# pcb_v1_4.net
KiCad netlist of a schematic drawn in EAGLE
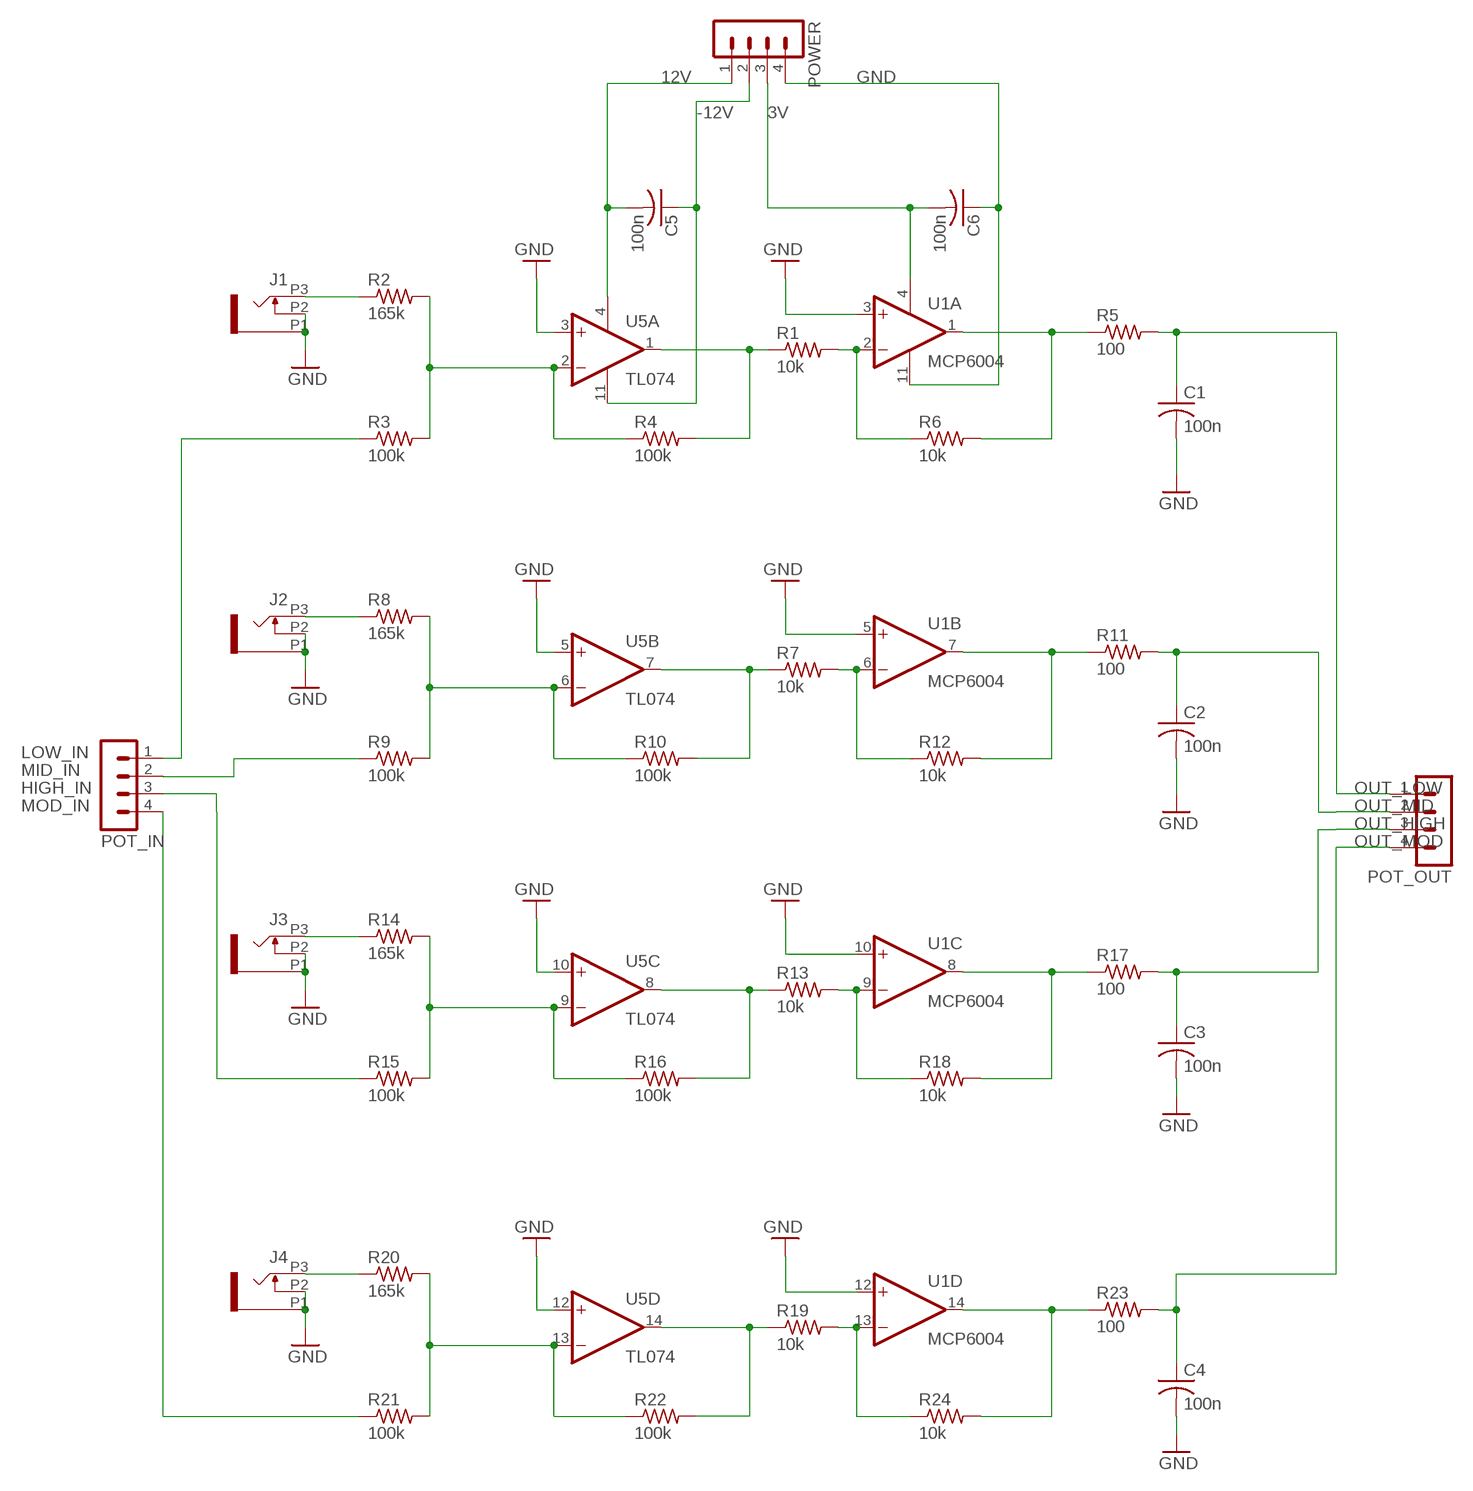
[diagram p0: schematic, sheet 1]

(export (version "E")
  (design (tool "Eeschema 10.0.6"))
  (components
    (comp (ref "C1")
      (value "100n")
      (footprint "eagle-import:C0603")
      (fields (field (name "SPICEPREFIX") "C"))
      (libsource (lib "eagle-import") (part "C-USC0603"))
    )
    (comp (ref "C2")
      (value "100n")
      (footprint "eagle-import:C0603")
      (fields (field (name "SPICEPREFIX") "C"))
      (libsource (lib "eagle-import") (part "C-USC0603"))
    )
    (comp (ref "C3")
      (value "100n")
      (footprint "eagle-import:C0603")
      (fields (field (name "SPICEPREFIX") "C"))
      (libsource (lib "eagle-import") (part "C-USC0603"))
    )
    (comp (ref "C4")
      (value "100n")
      (footprint "eagle-import:C0603")
      (fields (field (name "SPICEPREFIX") "C"))
      (libsource (lib "eagle-import") (part "C-USC0603"))
    )
    (comp (ref "C5")
      (value "100n")
      (footprint "eagle-import:C0603")
      (fields (field (name "SPICEPREFIX") "C"))
      (libsource (lib "eagle-import") (part "C-USC0603"))
    )
    (comp (ref "C6")
      (value "100n")
      (footprint "eagle-import:C0603")
      (fields (field (name "SPICEPREFIX") "C"))
      (libsource (lib "eagle-import") (part "C-USC0603"))
    )
    (comp (ref "J1")
      (value "PJ301_THONKICONN6")
      (footprint "eagle-import:WQP_PJ_301M6")
      (fields (field (name "SPICEPREFIX") "J"))
      (libsource (lib "eagle-import") (part "PJ301_THONKICONN6"))
    )
    (comp (ref "J2")
      (value "PJ301_THONKICONN6")
      (footprint "eagle-import:WQP_PJ_301M6")
      (fields (field (name "SPICEPREFIX") "J"))
      (libsource (lib "eagle-import") (part "PJ301_THONKICONN6"))
    )
    (comp (ref "J3")
      (value "PJ301_THONKICONN6")
      (footprint "eagle-import:WQP_PJ_301M6")
      (fields (field (name "SPICEPREFIX") "J"))
      (libsource (lib "eagle-import") (part "PJ301_THONKICONN6"))
    )
    (comp (ref "J4")
      (value "PJ301_THONKICONN6")
      (footprint "eagle-import:WQP_PJ_301M6")
      (fields (field (name "SPICEPREFIX") "J"))
      (libsource (lib "eagle-import") (part "PJ301_THONKICONN6"))
    )
    (comp (ref "POT_IN")
      (value "MA04-1")
      (footprint "eagle-import:MA04-1")
      (libsource (lib "eagle-import") (part "MA04-1"))
    )
    (comp (ref "POT_OUT")
      (value "MA04-1")
      (footprint "eagle-import:MA04-1")
      (libsource (lib "eagle-import") (part "MA04-1"))
    )
    (comp (ref "POWER")
      (value "MA04-1")
      (footprint "eagle-import:MA04-1")
      (libsource (lib "eagle-import") (part "MA04-1"))
    )
    (comp (ref "R1")
      (value "10k")
      (footprint "eagle-import:R0603")
      (fields (field (name "SPICEPREFIX") "R"))
      (libsource (lib "eagle-import") (part "R-US_R0603"))
    )
    (comp (ref "R2")
      (value "165k")
      (footprint "eagle-import:R0603")
      (fields (field (name "SPICEPREFIX") "R"))
      (libsource (lib "eagle-import") (part "R-US_R0603"))
    )
    (comp (ref "R3")
      (value "100k")
      (footprint "eagle-import:R0603")
      (fields (field (name "SPICEPREFIX") "R"))
      (libsource (lib "eagle-import") (part "R-US_R0603"))
    )
    (comp (ref "R4")
      (value "100k")
      (footprint "eagle-import:R0603")
      (fields (field (name "SPICEPREFIX") "R"))
      (libsource (lib "eagle-import") (part "R-US_R0603"))
    )
    (comp (ref "R5")
      (value "100")
      (footprint "eagle-import:R0603")
      (fields (field (name "SPICEPREFIX") "R"))
      (libsource (lib "eagle-import") (part "R-US_R0603"))
    )
    (comp (ref "R6")
      (value "10k")
      (footprint "eagle-import:R0603")
      (fields (field (name "SPICEPREFIX") "R"))
      (libsource (lib "eagle-import") (part "R-US_R0603"))
    )
    (comp (ref "R7")
      (value "10k")
      (footprint "eagle-import:R0603")
      (fields (field (name "SPICEPREFIX") "R"))
      (libsource (lib "eagle-import") (part "R-US_R0603"))
    )
    (comp (ref "R8")
      (value "165k")
      (footprint "eagle-import:R0603")
      (fields (field (name "SPICEPREFIX") "R"))
      (libsource (lib "eagle-import") (part "R-US_R0603"))
    )
    (comp (ref "R9")
      (value "100k")
      (footprint "eagle-import:R0603")
      (fields (field (name "SPICEPREFIX") "R"))
      (libsource (lib "eagle-import") (part "R-US_R0603"))
    )
    (comp (ref "R10")
      (value "100k")
      (footprint "eagle-import:R0603")
      (fields (field (name "SPICEPREFIX") "R"))
      (libsource (lib "eagle-import") (part "R-US_R0603"))
    )
    (comp (ref "R11")
      (value "100")
      (footprint "eagle-import:R0603")
      (fields (field (name "SPICEPREFIX") "R"))
      (libsource (lib "eagle-import") (part "R-US_R0603"))
    )
    (comp (ref "R12")
      (value "10k")
      (footprint "eagle-import:R0603")
      (fields (field (name "SPICEPREFIX") "R"))
      (libsource (lib "eagle-import") (part "R-US_R0603"))
    )
    (comp (ref "R13")
      (value "10k")
      (footprint "eagle-import:R0603")
      (fields (field (name "SPICEPREFIX") "R"))
      (libsource (lib "eagle-import") (part "R-US_R0603"))
    )
    (comp (ref "R14")
      (value "165k")
      (footprint "eagle-import:R0603")
      (fields (field (name "SPICEPREFIX") "R"))
      (libsource (lib "eagle-import") (part "R-US_R0603"))
    )
    (comp (ref "R15")
      (value "100k")
      (footprint "eagle-import:R0603")
      (fields (field (name "SPICEPREFIX") "R"))
      (libsource (lib "eagle-import") (part "R-US_R0603"))
    )
    (comp (ref "R16")
      (value "100k")
      (footprint "eagle-import:R0603")
      (fields (field (name "SPICEPREFIX") "R"))
      (libsource (lib "eagle-import") (part "R-US_R0603"))
    )
    (comp (ref "R17")
      (value "100")
      (footprint "eagle-import:R0603")
      (fields (field (name "SPICEPREFIX") "R"))
      (libsource (lib "eagle-import") (part "R-US_R0603"))
    )
    (comp (ref "R18")
      (value "10k")
      (footprint "eagle-import:R0603")
      (fields (field (name "SPICEPREFIX") "R"))
      (libsource (lib "eagle-import") (part "R-US_R0603"))
    )
    (comp (ref "R19")
      (value "10k")
      (footprint "eagle-import:R0603")
      (fields (field (name "SPICEPREFIX") "R"))
      (libsource (lib "eagle-import") (part "R-US_R0603"))
    )
    (comp (ref "R20")
      (value "165k")
      (footprint "eagle-import:R0603")
      (fields (field (name "SPICEPREFIX") "R"))
      (libsource (lib "eagle-import") (part "R-US_R0603"))
    )
    (comp (ref "R21")
      (value "100k")
      (footprint "eagle-import:R0603")
      (fields (field (name "SPICEPREFIX") "R"))
      (libsource (lib "eagle-import") (part "R-US_R0603"))
    )
    (comp (ref "R22")
      (value "100k")
      (footprint "eagle-import:R0603")
      (fields (field (name "SPICEPREFIX") "R"))
      (libsource (lib "eagle-import") (part "R-US_R0603"))
    )
    (comp (ref "R23")
      (value "100")
      (footprint "eagle-import:R0603")
      (fields (field (name "SPICEPREFIX") "R"))
      (libsource (lib "eagle-import") (part "R-US_R0603"))
    )
    (comp (ref "R24")
      (value "10k")
      (footprint "eagle-import:R0603")
      (fields (field (name "SPICEPREFIX") "R"))
      (libsource (lib "eagle-import") (part "R-US_R0603"))
    )
    (comp (ref "U1")
      (value "MCP6004")
      (footprint "eagle-import:SO14")
      (libsource (lib "eagle-import") (part "MCP6004_SMD"))
    )
    (comp (ref "U5")
      (value "TL074")
      (footprint "eagle-import:SO14")
      (libsource (lib "eagle-import") (part "TL074_SMD"))
    )
  )
  (nets
    (net (code "1") (name "/-12V") (class "Default")
      (node (ref "C5") (pin "1") (pinfunction "1_1") (pintype "passive"))
      (node (ref "POWER") (pin "2") (pinfunction "2_2") (pintype "passive"))
      (node (ref "U5") (pin "11") (pinfunction "V-_11") (pintype "power_in"))
    )
    (net (code "2") (name "/3V") (class "Default")
      (node (ref "C6") (pin "2") (pinfunction "2_2") (pintype "passive"))
      (node (ref "POWER") (pin "3") (pinfunction "3_3") (pintype "passive"))
      (node (ref "U1") (pin "4") (pinfunction "V+_4") (pintype "power_in"))
    )
    (net (code "3") (name "/12V") (class "Default")
      (node (ref "C5") (pin "2") (pinfunction "2_2") (pintype "passive"))
      (node (ref "POWER") (pin "1") (pinfunction "1_1") (pintype "passive"))
      (node (ref "U5") (pin "4") (pinfunction "V+_4") (pintype "power_in"))
    )
    (net (code "4") (name "/HIGH_IN") (class "Default")
      (node (ref "POT_IN") (pin "3") (pinfunction "3_3") (pintype "passive"))
      (node (ref "R15") (pin "1") (pinfunction "1_1") (pintype "passive"))
    )
    (net (code "5") (name "/LOW_IN") (class "Default")
      (node (ref "POT_IN") (pin "1") (pinfunction "1_1") (pintype "passive"))
      (node (ref "R3") (pin "1") (pinfunction "1_1") (pintype "passive"))
    )
    (net (code "6") (name "/MID_IN") (class "Default")
      (node (ref "POT_IN") (pin "2") (pinfunction "2_2") (pintype "passive"))
      (node (ref "R9") (pin "1") (pinfunction "1_1") (pintype "passive"))
    )
    (net (code "7") (name "/MOD_IN") (class "Default")
      (node (ref "POT_IN") (pin "4") (pinfunction "4_4") (pintype "passive"))
      (node (ref "R21") (pin "1") (pinfunction "1_1") (pintype "passive"))
    )
    (net (code "8") (name "/OUT_HIGH") (class "Default")
      (node (ref "C3") (pin "1") (pinfunction "1_1") (pintype "passive"))
      (node (ref "POT_OUT") (pin "3") (pinfunction "3_3") (pintype "passive"))
      (node (ref "R17") (pin "2") (pinfunction "2_2") (pintype "passive"))
    )
    (net (code "9") (name "/OUT_LOW") (class "Default")
      (node (ref "C1") (pin "1") (pinfunction "1_1") (pintype "passive"))
      (node (ref "POT_OUT") (pin "1") (pinfunction "1_1") (pintype "passive"))
      (node (ref "R5") (pin "2") (pinfunction "2_2") (pintype "passive"))
    )
    (net (code "10") (name "/OUT_MID") (class "Default")
      (node (ref "C2") (pin "1") (pinfunction "1_1") (pintype "passive"))
      (node (ref "POT_OUT") (pin "2") (pinfunction "2_2") (pintype "passive"))
      (node (ref "R11") (pin "2") (pinfunction "2_2") (pintype "passive"))
    )
    (net (code "11") (name "/OUT_MOD") (class "Default")
      (node (ref "C4") (pin "1") (pinfunction "1_1") (pintype "passive"))
      (node (ref "POT_OUT") (pin "4") (pinfunction "4_4") (pintype "passive"))
      (node (ref "R23") (pin "2") (pinfunction "2_2") (pintype "passive"))
    )
    (net (code "12") (name "GND") (class "Default")
      (node (ref "C1") (pin "2") (pinfunction "2_2") (pintype "passive"))
      (node (ref "C2") (pin "2") (pinfunction "2_2") (pintype "passive"))
      (node (ref "C3") (pin "2") (pinfunction "2_2") (pintype "passive"))
      (node (ref "C4") (pin "2") (pinfunction "2_2") (pintype "passive"))
      (node (ref "C6") (pin "1") (pinfunction "1_1") (pintype "passive"))
      (node (ref "J1") (pin "P1") (pinfunction "1_P1") (pintype "passive"))
      (node (ref "J1") (pin "P2") (pinfunction "2_P2") (pintype "passive"))
      (node (ref "J2") (pin "P1") (pinfunction "1_P1") (pintype "passive"))
      (node (ref "J2") (pin "P2") (pinfunction "2_P2") (pintype "passive"))
      (node (ref "J3") (pin "P1") (pinfunction "1_P1") (pintype "passive"))
      (node (ref "J3") (pin "P2") (pinfunction "2_P2") (pintype "passive"))
      (node (ref "J4") (pin "P1") (pinfunction "1_P1") (pintype "passive"))
      (node (ref "J4") (pin "P2") (pinfunction "2_P2") (pintype "passive"))
      (node (ref "POWER") (pin "4") (pinfunction "4_4") (pintype "passive"))
      (node (ref "U1") (pin "10") (pinfunction "+IN_10") (pintype "input"))
      (node (ref "U1") (pin "11") (pinfunction "V-_11") (pintype "power_in"))
      (node (ref "U1") (pin "12") (pinfunction "+IN_12") (pintype "input"))
      (node (ref "U1") (pin "3") (pinfunction "+IN_3") (pintype "input"))
      (node (ref "U1") (pin "5") (pinfunction "+IN_5") (pintype "input"))
      (node (ref "U5") (pin "10") (pinfunction "+IN_10") (pintype "input"))
      (node (ref "U5") (pin "12") (pinfunction "+IN_12") (pintype "input"))
      (node (ref "U5") (pin "3") (pinfunction "+IN_3") (pintype "input"))
      (node (ref "U5") (pin "5") (pinfunction "+IN_5") (pintype "input"))
    )
    (net (code "13") (name "Net-(J1-3)") (class "Default")
      (node (ref "J1") (pin "P3") (pinfunction "3_P3") (pintype "passive"))
      (node (ref "R2") (pin "1") (pinfunction "1_1") (pintype "passive"))
    )
    (net (code "14") (name "Net-(J2-3)") (class "Default")
      (node (ref "J2") (pin "P3") (pinfunction "3_P3") (pintype "passive"))
      (node (ref "R8") (pin "1") (pinfunction "1_1") (pintype "passive"))
    )
    (net (code "15") (name "Net-(J3-3)") (class "Default")
      (node (ref "J3") (pin "P3") (pinfunction "3_P3") (pintype "passive"))
      (node (ref "R14") (pin "1") (pinfunction "1_1") (pintype "passive"))
    )
    (net (code "16") (name "Net-(J4-3)") (class "Default")
      (node (ref "J4") (pin "P3") (pinfunction "3_P3") (pintype "passive"))
      (node (ref "R20") (pin "1") (pinfunction "1_1") (pintype "passive"))
    )
    (net (code "17") (name "Net-(U1A--IN)") (class "Default")
      (node (ref "R1") (pin "2") (pinfunction "2_2") (pintype "passive"))
      (node (ref "R6") (pin "1") (pinfunction "1_1") (pintype "passive"))
      (node (ref "U1") (pin "2") (pinfunction "-IN_2") (pintype "input"))
    )
    (net (code "18") (name "Net-(U1A-OUT)") (class "Default")
      (node (ref "R5") (pin "1") (pinfunction "1_1") (pintype "passive"))
      (node (ref "R6") (pin "2") (pinfunction "2_2") (pintype "passive"))
      (node (ref "U1") (pin "1") (pinfunction "OUT_1") (pintype "output"))
    )
    (net (code "19") (name "Net-(U1B--IN)") (class "Default")
      (node (ref "R12") (pin "1") (pinfunction "1_1") (pintype "passive"))
      (node (ref "R7") (pin "2") (pinfunction "2_2") (pintype "passive"))
      (node (ref "U1") (pin "6") (pinfunction "-IN_6") (pintype "input"))
    )
    (net (code "20") (name "Net-(U1B-OUT)") (class "Default")
      (node (ref "R11") (pin "1") (pinfunction "1_1") (pintype "passive"))
      (node (ref "R12") (pin "2") (pinfunction "2_2") (pintype "passive"))
      (node (ref "U1") (pin "7") (pinfunction "OUT_7") (pintype "output"))
    )
    (net (code "21") (name "Net-(U1C--IN)") (class "Default")
      (node (ref "R13") (pin "2") (pinfunction "2_2") (pintype "passive"))
      (node (ref "R18") (pin "1") (pinfunction "1_1") (pintype "passive"))
      (node (ref "U1") (pin "9") (pinfunction "-IN_9") (pintype "input"))
    )
    (net (code "22") (name "Net-(U1C-OUT)") (class "Default")
      (node (ref "R17") (pin "1") (pinfunction "1_1") (pintype "passive"))
      (node (ref "R18") (pin "2") (pinfunction "2_2") (pintype "passive"))
      (node (ref "U1") (pin "8") (pinfunction "OUT_8") (pintype "output"))
    )
    (net (code "23") (name "Net-(U1D--IN)") (class "Default")
      (node (ref "R19") (pin "2") (pinfunction "2_2") (pintype "passive"))
      (node (ref "R24") (pin "1") (pinfunction "1_1") (pintype "passive"))
      (node (ref "U1") (pin "13") (pinfunction "-IN_13") (pintype "input"))
    )
    (net (code "24") (name "Net-(U1D-OUT)") (class "Default")
      (node (ref "R23") (pin "1") (pinfunction "1_1") (pintype "passive"))
      (node (ref "R24") (pin "2") (pinfunction "2_2") (pintype "passive"))
      (node (ref "U1") (pin "14") (pinfunction "OUT_14") (pintype "output"))
    )
    (net (code "25") (name "Net-(U5A--IN)") (class "Default")
      (node (ref "R2") (pin "2") (pinfunction "2_2") (pintype "passive"))
      (node (ref "R3") (pin "2") (pinfunction "2_2") (pintype "passive"))
      (node (ref "R4") (pin "1") (pinfunction "1_1") (pintype "passive"))
      (node (ref "U5") (pin "2") (pinfunction "-IN_2") (pintype "input"))
    )
    (net (code "26") (name "Net-(U5A-OUT)") (class "Default")
      (node (ref "R1") (pin "1") (pinfunction "1_1") (pintype "passive"))
      (node (ref "R4") (pin "2") (pinfunction "2_2") (pintype "passive"))
      (node (ref "U5") (pin "1") (pinfunction "OUT_1") (pintype "output"))
    )
    (net (code "27") (name "Net-(U5B--IN)") (class "Default")
      (node (ref "R10") (pin "1") (pinfunction "1_1") (pintype "passive"))
      (node (ref "R8") (pin "2") (pinfunction "2_2") (pintype "passive"))
      (node (ref "R9") (pin "2") (pinfunction "2_2") (pintype "passive"))
      (node (ref "U5") (pin "6") (pinfunction "-IN_6") (pintype "input"))
    )
    (net (code "28") (name "Net-(U5B-OUT)") (class "Default")
      (node (ref "R10") (pin "2") (pinfunction "2_2") (pintype "passive"))
      (node (ref "R7") (pin "1") (pinfunction "1_1") (pintype "passive"))
      (node (ref "U5") (pin "7") (pinfunction "OUT_7") (pintype "output"))
    )
    (net (code "29") (name "Net-(U5C--IN)") (class "Default")
      (node (ref "R14") (pin "2") (pinfunction "2_2") (pintype "passive"))
      (node (ref "R15") (pin "2") (pinfunction "2_2") (pintype "passive"))
      (node (ref "R16") (pin "1") (pinfunction "1_1") (pintype "passive"))
      (node (ref "U5") (pin "9") (pinfunction "-IN_9") (pintype "input"))
    )
    (net (code "30") (name "Net-(U5C-OUT)") (class "Default")
      (node (ref "R13") (pin "1") (pinfunction "1_1") (pintype "passive"))
      (node (ref "R16") (pin "2") (pinfunction "2_2") (pintype "passive"))
      (node (ref "U5") (pin "8") (pinfunction "OUT_8") (pintype "output"))
    )
    (net (code "31") (name "Net-(U5D--IN)") (class "Default")
      (node (ref "R20") (pin "2") (pinfunction "2_2") (pintype "passive"))
      (node (ref "R21") (pin "2") (pinfunction "2_2") (pintype "passive"))
      (node (ref "R22") (pin "1") (pinfunction "1_1") (pintype "passive"))
      (node (ref "U5") (pin "13") (pinfunction "-IN_13") (pintype "input"))
    )
    (net (code "32") (name "Net-(U5D-OUT)") (class "Default")
      (node (ref "R19") (pin "1") (pinfunction "1_1") (pintype "passive"))
      (node (ref "R22") (pin "2") (pinfunction "2_2") (pintype "passive"))
      (node (ref "U5") (pin "14") (pinfunction "OUT_14") (pintype "output"))
    )
  )
)
